# BT_last_version.net
KiCad netlist of a schematic drawn in EAGLE
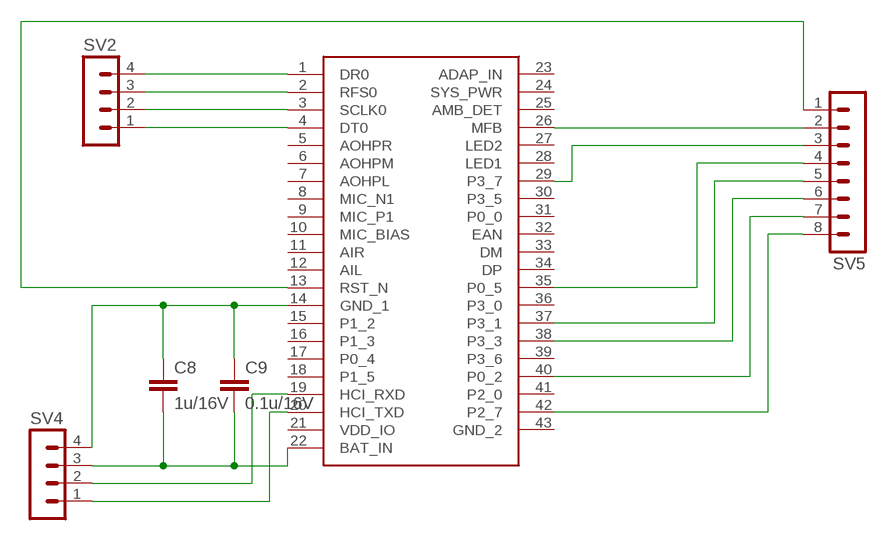
[diagram p0: schematic, sheet 1]

(export (version "E")
  (design (tool "Eeschema 10.0.6"))
  (components
    (comp (ref "ANT2")
      (value "BM64SPKS1MC2-0001AA")
      (footprint "eagle-import:BM64SPKS1MC20001AA")
      (fields (field (name "MF") "Microchip"))
      (libsource (lib "eagle-import") (part "BM64SPKS1MC2-0001AA"))
    )
    (comp (ref "C8")
      (value "1u/16V")
      (footprint "eagle-import:C2.5-3")
      (libsource (lib "eagle-import") (part "C2,5-3"))
    )
    (comp (ref "C9")
      (value "0.1u/16V")
      (footprint "eagle-import:C2.5-3")
      (libsource (lib "eagle-import") (part "C2,5-3"))
    )
    (comp (ref "SV2")
      (value "MA04-1")
      (footprint "eagle-import:MA04-1")
      (libsource (lib "eagle-import") (part "MA04-1"))
    )
    (comp (ref "SV4")
      (value "MA04-1")
      (footprint "eagle-import:MA04-1")
      (libsource (lib "eagle-import") (part "MA04-1"))
    )
    (comp (ref "SV5")
      (value "MA08-1W")
      (footprint "eagle-import:MA08-1W")
      (libsource (lib "eagle-import") (part "MA08-1W"))
    )
  )
  (nets
    (net (code "1") (name "Net-(ANT2-BAT_IN)") (class "Default")
      (node (ref "ANT2") (pin "22") (pinfunction "BAT_IN_22") (pintype "bidirectional"))
      (node (ref "C8") (pin "2") (pinfunction "2_2") (pintype "passive"))
      (node (ref "C9") (pin "2") (pinfunction "2_2") (pintype "passive"))
      (node (ref "SV4") (pin "3") (pinfunction "3_3") (pintype "passive"))
    )
    (net (code "2") (name "Net-(ANT2-DR0)") (class "Default")
      (node (ref "ANT2") (pin "1") (pinfunction "DR0_1") (pintype "bidirectional"))
      (node (ref "SV2") (pin "4") (pinfunction "4_4") (pintype "passive"))
    )
    (net (code "3") (name "Net-(ANT2-DT0)") (class "Default")
      (node (ref "ANT2") (pin "4") (pinfunction "DT0_4") (pintype "bidirectional"))
      (node (ref "SV2") (pin "1") (pinfunction "1_1") (pintype "passive"))
    )
    (net (code "4") (name "Net-(ANT2-GND_1)") (class "Default")
      (node (ref "ANT2") (pin "14") (pinfunction "GND_1_14") (pintype "bidirectional"))
      (node (ref "C8") (pin "1") (pinfunction "1_1") (pintype "passive"))
      (node (ref "C9") (pin "1") (pinfunction "1_1") (pintype "passive"))
      (node (ref "SV4") (pin "4") (pinfunction "4_4") (pintype "passive"))
    )
    (net (code "5") (name "Net-(ANT2-HCI_RXD)") (class "Default")
      (node (ref "ANT2") (pin "19") (pinfunction "HCI_RXD_19") (pintype "bidirectional"))
      (node (ref "SV4") (pin "2") (pinfunction "2_2") (pintype "passive"))
    )
    (net (code "6") (name "Net-(ANT2-HCI_TXD)") (class "Default")
      (node (ref "ANT2") (pin "20") (pinfunction "HCI_TXD_20") (pintype "bidirectional"))
      (node (ref "SV4") (pin "1") (pinfunction "1_1") (pintype "passive"))
    )
    (net (code "7") (name "Net-(ANT2-MFB)") (class "Default")
      (node (ref "ANT2") (pin "26") (pinfunction "MFB_26") (pintype "bidirectional"))
      (node (ref "SV5") (pin "2") (pinfunction "2_2") (pintype "passive"))
    )
    (net (code "8") (name "Net-(ANT2-P0_2)") (class "Default")
      (node (ref "ANT2") (pin "40") (pinfunction "P0_2_40") (pintype "bidirectional"))
      (node (ref "SV5") (pin "7") (pinfunction "7_7") (pintype "passive"))
    )
    (net (code "9") (name "Net-(ANT2-P0_5)") (class "Default")
      (node (ref "ANT2") (pin "35") (pinfunction "P0_5_35") (pintype "bidirectional"))
      (node (ref "SV5") (pin "4") (pinfunction "4_4") (pintype "passive"))
    )
    (net (code "10") (name "Net-(ANT2-P2_7)") (class "Default")
      (node (ref "ANT2") (pin "42") (pinfunction "P2_7_42") (pintype "bidirectional"))
      (node (ref "SV5") (pin "8") (pinfunction "8_8") (pintype "passive"))
    )
    (net (code "11") (name "Net-(ANT2-P3_1)") (class "Default")
      (node (ref "ANT2") (pin "37") (pinfunction "P3_1_37") (pintype "bidirectional"))
      (node (ref "SV5") (pin "5") (pinfunction "5_5") (pintype "passive"))
    )
    (net (code "12") (name "Net-(ANT2-P3_3)") (class "Default")
      (node (ref "ANT2") (pin "38") (pinfunction "P3_3_38") (pintype "bidirectional"))
      (node (ref "SV5") (pin "6") (pinfunction "6_6") (pintype "passive"))
    )
    (net (code "13") (name "Net-(ANT2-P3_7)") (class "Default")
      (node (ref "ANT2") (pin "29") (pinfunction "P3_7_29") (pintype "bidirectional"))
      (node (ref "SV5") (pin "3") (pinfunction "3_3") (pintype "passive"))
    )
    (net (code "14") (name "Net-(ANT2-RFS0)") (class "Default")
      (node (ref "ANT2") (pin "2") (pinfunction "RFS0_2") (pintype "bidirectional"))
      (node (ref "SV2") (pin "3") (pinfunction "3_3") (pintype "passive"))
    )
    (net (code "15") (name "Net-(ANT2-RST_N)") (class "Default")
      (node (ref "ANT2") (pin "13") (pinfunction "RST_N_13") (pintype "bidirectional"))
      (node (ref "SV5") (pin "1") (pinfunction "1_1") (pintype "passive"))
    )
    (net (code "16") (name "Net-(ANT2-SCLK0)") (class "Default")
      (node (ref "ANT2") (pin "3") (pinfunction "SCLK0_3") (pintype "bidirectional"))
      (node (ref "SV2") (pin "2") (pinfunction "2_2") (pintype "passive"))
    )
    (net (code "17") (name "unconnected-(ANT2-ADAP_IN-Pad23)") (class "Default")
      (node (ref "ANT2") (pin "23") (pinfunction "ADAP_IN_23") (pintype "bidirectional"))
    )
    (net (code "18") (name "unconnected-(ANT2-AIL-Pad12)") (class "Default")
      (node (ref "ANT2") (pin "12") (pinfunction "AIL_12") (pintype "bidirectional"))
    )
    (net (code "19") (name "unconnected-(ANT2-AIR-Pad11)") (class "Default")
      (node (ref "ANT2") (pin "11") (pinfunction "AIR_11") (pintype "bidirectional"))
    )
    (net (code "20") (name "unconnected-(ANT2-AMB_DET-Pad25)") (class "Default")
      (node (ref "ANT2") (pin "25") (pinfunction "AMB_DET_25") (pintype "bidirectional"))
    )
    (net (code "21") (name "unconnected-(ANT2-AOHPL-Pad7)") (class "Default")
      (node (ref "ANT2") (pin "7") (pinfunction "AOHPL_7") (pintype "bidirectional"))
    )
    (net (code "22") (name "unconnected-(ANT2-AOHPM-Pad6)") (class "Default")
      (node (ref "ANT2") (pin "6") (pinfunction "AOHPM_6") (pintype "bidirectional"))
    )
    (net (code "23") (name "unconnected-(ANT2-AOHPR-Pad5)") (class "Default")
      (node (ref "ANT2") (pin "5") (pinfunction "AOHPR_5") (pintype "bidirectional"))
    )
    (net (code "24") (name "unconnected-(ANT2-DM-Pad33)") (class "Default")
      (node (ref "ANT2") (pin "33") (pinfunction "DM_33") (pintype "bidirectional"))
    )
    (net (code "25") (name "unconnected-(ANT2-DP-Pad34)") (class "Default")
      (node (ref "ANT2") (pin "34") (pinfunction "DP_34") (pintype "bidirectional"))
    )
    (net (code "26") (name "unconnected-(ANT2-EAN-Pad32)") (class "Default")
      (node (ref "ANT2") (pin "32") (pinfunction "EAN_32") (pintype "bidirectional"))
    )
    (net (code "27") (name "unconnected-(ANT2-GND_2-Pad43)") (class "Default")
      (node (ref "ANT2") (pin "43") (pinfunction "GND_2_43") (pintype "bidirectional"))
    )
    (net (code "28") (name "unconnected-(ANT2-LED1-Pad28)") (class "Default")
      (node (ref "ANT2") (pin "28") (pinfunction "LED1_28") (pintype "bidirectional"))
    )
    (net (code "29") (name "unconnected-(ANT2-LED2-Pad27)") (class "Default")
      (node (ref "ANT2") (pin "27") (pinfunction "LED2_27") (pintype "bidirectional"))
    )
    (net (code "30") (name "unconnected-(ANT2-MIC_BIAS-Pad10)") (class "Default")
      (node (ref "ANT2") (pin "10") (pinfunction "MIC_BIAS_10") (pintype "bidirectional"))
    )
    (net (code "31") (name "unconnected-(ANT2-MIC_N1-Pad8)") (class "Default")
      (node (ref "ANT2") (pin "8") (pinfunction "MIC_N1_8") (pintype "bidirectional"))
    )
    (net (code "32") (name "unconnected-(ANT2-MIC_P1-Pad9)") (class "Default")
      (node (ref "ANT2") (pin "9") (pinfunction "MIC_P1_9") (pintype "bidirectional"))
    )
    (net (code "33") (name "unconnected-(ANT2-P0_0-Pad31)") (class "Default")
      (node (ref "ANT2") (pin "31") (pinfunction "P0_0_31") (pintype "bidirectional"))
    )
    (net (code "34") (name "unconnected-(ANT2-P0_4-Pad17)") (class "Default")
      (node (ref "ANT2") (pin "17") (pinfunction "P0_4_17") (pintype "bidirectional"))
    )
    (net (code "35") (name "unconnected-(ANT2-P1_2-Pad15)") (class "Default")
      (node (ref "ANT2") (pin "15") (pinfunction "P1_2_15") (pintype "bidirectional"))
    )
    (net (code "36") (name "unconnected-(ANT2-P1_3-Pad16)") (class "Default")
      (node (ref "ANT2") (pin "16") (pinfunction "P1_3_16") (pintype "bidirectional"))
    )
    (net (code "37") (name "unconnected-(ANT2-P1_5-Pad18)") (class "Default")
      (node (ref "ANT2") (pin "18") (pinfunction "P1_5_18") (pintype "bidirectional"))
    )
    (net (code "38") (name "unconnected-(ANT2-P2_0-Pad41)") (class "Default")
      (node (ref "ANT2") (pin "41") (pinfunction "P2_0_41") (pintype "bidirectional"))
    )
    (net (code "39") (name "unconnected-(ANT2-P3_0-Pad36)") (class "Default")
      (node (ref "ANT2") (pin "36") (pinfunction "P3_0_36") (pintype "bidirectional"))
    )
    (net (code "40") (name "unconnected-(ANT2-P3_5-Pad30)") (class "Default")
      (node (ref "ANT2") (pin "30") (pinfunction "P3_5_30") (pintype "bidirectional"))
    )
    (net (code "41") (name "unconnected-(ANT2-P3_6-Pad39)") (class "Default")
      (node (ref "ANT2") (pin "39") (pinfunction "P3_6_39") (pintype "bidirectional"))
    )
    (net (code "42") (name "unconnected-(ANT2-SYS_PWR-Pad24)") (class "Default")
      (node (ref "ANT2") (pin "24") (pinfunction "SYS_PWR_24") (pintype "bidirectional"))
    )
    (net (code "43") (name "unconnected-(ANT2-VDD_IO-Pad21)") (class "Default")
      (node (ref "ANT2") (pin "21") (pinfunction "VDD_IO_21") (pintype "bidirectional"))
    )
  )
)
